# Group_Project_PCB_Updated.net
KiCad netlist of a schematic drawn in EAGLE
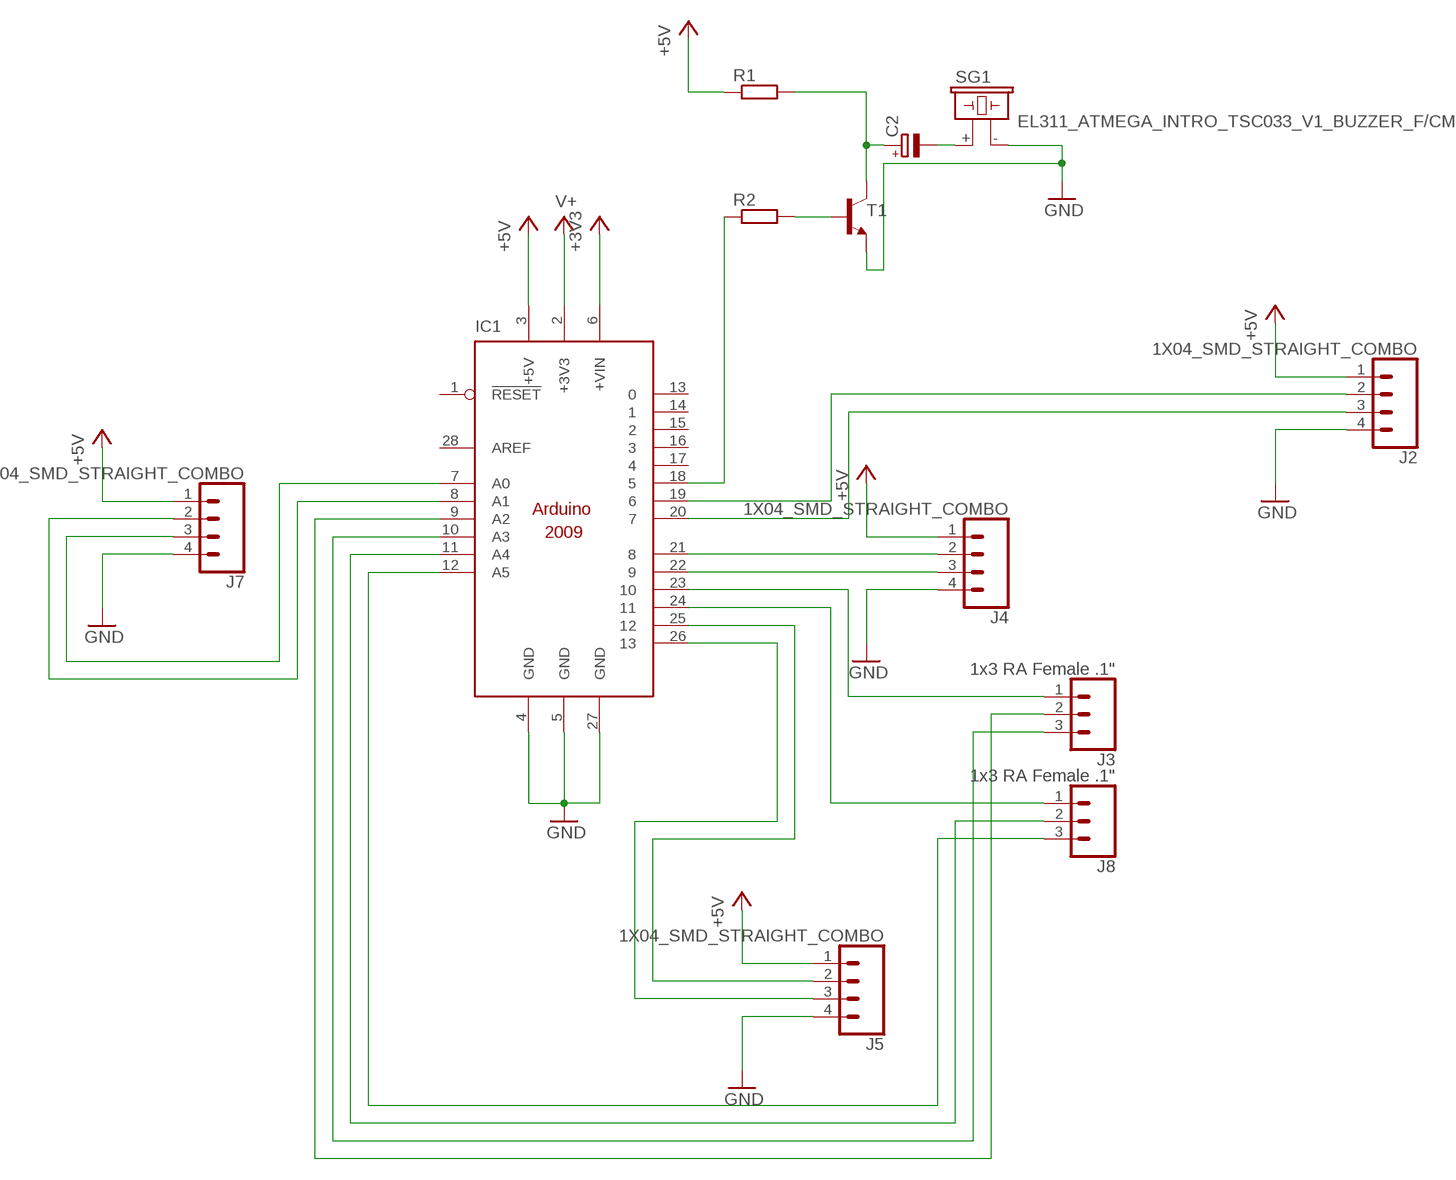
[diagram p0: schematic, sheet 1]

(export (version "E")
  (design (tool "Eeschema 10.0.6"))
  (components
    (comp (ref "C2")
      (value "RCL_CPOL-EUE3.5-8")
      (footprint "eagle-import:ELECTROLYTIC_CAP_RCL_E3,5-8")
      (libsource (lib "eagle-import") (part "RCL_CPOL-EUE3.5-8"))
    )
    (comp (ref "IC1")
      (value "ARDUINO2009_10")
      (footprint "eagle-import:ARDUINO2009")
      (libsource (lib "eagle-import") (part "ARDUINO2009_10"))
    )
    (comp (ref "J2")
      (value "1X04_SMD_STRAIGHT_COMBO")
      (footprint "eagle-import:1X04_LONGPADS")
      (libsource (lib "eagle-import") (part "CONN_04LONGPADS"))
    )
    (comp (ref "J3")
      (value "1x3 RA Female .1\"")
      (footprint "eagle-import:1X03_LONGPADS")
      (libsource (lib "eagle-import") (part "CONN_03LONGPADS"))
    )
    (comp (ref "J4")
      (value "1X04_SMD_STRAIGHT_COMBO")
      (footprint "eagle-import:1X04_LONGPADS")
      (libsource (lib "eagle-import") (part "CONN_04LONGPADS"))
    )
    (comp (ref "J5")
      (value "1X04_SMD_STRAIGHT_COMBO")
      (footprint "eagle-import:1X04_LONGPADS")
      (libsource (lib "eagle-import") (part "CONN_04LONGPADS"))
    )
    (comp (ref "J7")
      (value "1X04_SMD_STRAIGHT_COMBO")
      (footprint "eagle-import:1X04_LONGPADS")
      (libsource (lib "eagle-import") (part "CONN_04LONGPADS"))
    )
    (comp (ref "J8")
      (value "1x3 RA Female .1\"")
      (footprint "eagle-import:1X03_LONGPADS")
      (libsource (lib "eagle-import") (part "CONN_03LONGPADS"))
    )
    (comp (ref "R1")
      (value "R-EU_0207/10")
      (footprint "eagle-import:0207_10")
      (libsource (lib "eagle-import") (part "R-EU_0207/10"))
    )
    (comp (ref "R2")
      (value "R-EU_0207/10")
      (footprint "eagle-import:0207_10")
      (libsource (lib "eagle-import") (part "R-EU_0207/10"))
    )
    (comp (ref "SG1")
      (value "EL311_ATMEGA_INTRO_TSC033_V1_BUZZER_F/CM12P")
      (footprint "eagle-import:EL311_ATMEGA_INTRO_TSC033_V1_BUZZER_F_CM12P")
      (libsource (lib "eagle-import") (part "EL311_ATMEGA_INTRO_TSC033_V1_BUZZER_F/CM12P"))
    )
    (comp (ref "T1")
      (value "2N1613-NPN-TO92-EBC")
      (footprint "eagle-import:TO92-EBC")
      (libsource (lib "eagle-import") (part "-NPN-TO92-EBC2N1613"))
    )
  )
  (nets
    (net (code "1") (name "+3V3") (class "Default")
      (node (ref "IC1") (pin "6") (pinfunction "+VIN_6") (pintype "bidirectional"))
    )
    (net (code "2") (name "+5V") (class "Default")
      (node (ref "IC1") (pin "3") (pinfunction "+5V_3") (pintype "power_in"))
      (node (ref "J2") (pin "1") (pinfunction "1_1") (pintype "passive"))
      (node (ref "J4") (pin "1") (pinfunction "1_1") (pintype "passive"))
      (node (ref "J5") (pin "1") (pinfunction "1_1") (pintype "passive"))
      (node (ref "J7") (pin "1") (pinfunction "1_1") (pintype "passive"))
      (node (ref "R1") (pin "1") (pinfunction "1_1") (pintype "passive"))
    )
    (net (code "3") (name "GND") (class "Default")
      (node (ref "IC1") (pin "27") (pinfunction "GND_27") (pintype "power_in"))
      (node (ref "IC1") (pin "4") (pinfunction "GND_4") (pintype "power_in"))
      (node (ref "IC1") (pin "5") (pinfunction "GND_5") (pintype "power_in"))
      (node (ref "J2") (pin "4") (pinfunction "4_4") (pintype "passive"))
      (node (ref "J4") (pin "4") (pinfunction "4_4") (pintype "passive"))
      (node (ref "J5") (pin "4") (pinfunction "4_4") (pintype "passive"))
      (node (ref "J7") (pin "4") (pinfunction "4_4") (pintype "passive"))
      (node (ref "SG1") (pin "-") (pinfunction "2_-") (pintype "passive"))
      (node (ref "T1") (pin "E") (pinfunction "E_E") (pintype "passive"))
    )
    (net (code "4") (name "Net-(C2-Pad+)") (class "Default")
      (node (ref "C2") (pin "+") (pinfunction "+_+") (pintype "passive"))
      (node (ref "R1") (pin "2") (pinfunction "2_2") (pintype "passive"))
      (node (ref "T1") (pin "C") (pinfunction "C_C") (pintype "passive"))
    )
    (net (code "5") (name "Net-(IC1-5)") (class "Default")
      (node (ref "IC1") (pin "18") (pinfunction "5_18") (pintype "bidirectional"))
      (node (ref "R2") (pin "1") (pinfunction "1_1") (pintype "passive"))
    )
    (net (code "6") (name "Net-(IC1-6)") (class "Default")
      (node (ref "IC1") (pin "19") (pinfunction "6_19") (pintype "bidirectional"))
      (node (ref "J2") (pin "2") (pinfunction "2_2") (pintype "passive"))
    )
    (net (code "7") (name "Net-(IC1-7)") (class "Default")
      (node (ref "IC1") (pin "20") (pinfunction "7_20") (pintype "bidirectional"))
      (node (ref "J2") (pin "3") (pinfunction "3_3") (pintype "passive"))
    )
    (net (code "8") (name "Net-(IC1-8)") (class "Default")
      (node (ref "IC1") (pin "21") (pinfunction "8_21") (pintype "bidirectional"))
      (node (ref "J4") (pin "2") (pinfunction "2_2") (pintype "passive"))
    )
    (net (code "9") (name "Net-(IC1-9)") (class "Default")
      (node (ref "IC1") (pin "22") (pinfunction "9_22") (pintype "bidirectional"))
      (node (ref "J4") (pin "3") (pinfunction "3_3") (pintype "passive"))
    )
    (net (code "10") (name "Net-(IC1-10)") (class "Default")
      (node (ref "IC1") (pin "23") (pinfunction "10_23") (pintype "bidirectional"))
      (node (ref "J3") (pin "1") (pinfunction "1_1") (pintype "passive"))
    )
    (net (code "11") (name "Net-(IC1-11)") (class "Default")
      (node (ref "IC1") (pin "24") (pinfunction "11_24") (pintype "bidirectional"))
      (node (ref "J8") (pin "1") (pinfunction "1_1") (pintype "passive"))
    )
    (net (code "12") (name "Net-(IC1-12)") (class "Default")
      (node (ref "IC1") (pin "25") (pinfunction "12_25") (pintype "bidirectional"))
      (node (ref "J5") (pin "2") (pinfunction "2_2") (pintype "passive"))
    )
    (net (code "13") (name "Net-(IC1-13)") (class "Default")
      (node (ref "IC1") (pin "26") (pinfunction "13_26") (pintype "bidirectional"))
      (node (ref "J5") (pin "3") (pinfunction "3_3") (pintype "passive"))
    )
    (net (code "14") (name "Net-(IC1-A0)") (class "Default")
      (node (ref "IC1") (pin "7") (pinfunction "A0_7") (pintype "bidirectional"))
      (node (ref "J7") (pin "3") (pinfunction "3_3") (pintype "passive"))
    )
    (net (code "15") (name "Net-(IC1-A1)") (class "Default")
      (node (ref "IC1") (pin "8") (pinfunction "A1_8") (pintype "bidirectional"))
      (node (ref "J7") (pin "2") (pinfunction "2_2") (pintype "passive"))
    )
    (net (code "16") (name "Net-(IC1-A2)") (class "Default")
      (node (ref "IC1") (pin "9") (pinfunction "A2_9") (pintype "bidirectional"))
      (node (ref "J3") (pin "2") (pinfunction "2_2") (pintype "passive"))
    )
    (net (code "17") (name "Net-(IC1-A3)") (class "Default")
      (node (ref "IC1") (pin "10") (pinfunction "A3_10") (pintype "bidirectional"))
      (node (ref "J3") (pin "3") (pinfunction "3_3") (pintype "passive"))
    )
    (net (code "18") (name "Net-(IC1-A4)") (class "Default")
      (node (ref "IC1") (pin "11") (pinfunction "A4_11") (pintype "bidirectional"))
      (node (ref "J8") (pin "2") (pinfunction "2_2") (pintype "passive"))
    )
    (net (code "19") (name "Net-(IC1-A5)") (class "Default")
      (node (ref "IC1") (pin "12") (pinfunction "A5_12") (pintype "bidirectional"))
      (node (ref "J8") (pin "3") (pinfunction "3_3") (pintype "passive"))
    )
    (net (code "20") (name "Net-(R2-Pad2)") (class "Default")
      (node (ref "R2") (pin "2") (pinfunction "2_2") (pintype "passive"))
      (node (ref "T1") (pin "B") (pinfunction "B_B") (pintype "passive"))
    )
    (net (code "21") (name "Net-(SG1-1)") (class "Default")
      (node (ref "C2") (pin "-") (pinfunction "-_-") (pintype "passive"))
      (node (ref "SG1") (pin "+") (pinfunction "1_+") (pintype "passive"))
    )
    (net (code "22") (name "V+") (class "Default")
      (node (ref "IC1") (pin "2") (pinfunction "+3V3_2") (pintype "power_in"))
    )
    (net (code "23") (name "unconnected-(IC1-0-Pad13)") (class "Default")
      (node (ref "IC1") (pin "13") (pinfunction "0_13") (pintype "bidirectional"))
    )
    (net (code "24") (name "unconnected-(IC1-1-Pad14)") (class "Default")
      (node (ref "IC1") (pin "14") (pinfunction "1_14") (pintype "bidirectional"))
    )
    (net (code "25") (name "unconnected-(IC1-2-Pad15)") (class "Default")
      (node (ref "IC1") (pin "15") (pinfunction "2_15") (pintype "bidirectional"))
    )
    (net (code "26") (name "unconnected-(IC1-3-Pad16)") (class "Default")
      (node (ref "IC1") (pin "16") (pinfunction "3_16") (pintype "bidirectional"))
    )
    (net (code "27") (name "unconnected-(IC1-4-Pad17)") (class "Default")
      (node (ref "IC1") (pin "17") (pinfunction "4_17") (pintype "bidirectional"))
    )
    (net (code "28") (name "unconnected-(IC1-AREF-Pad28)") (class "Default")
      (node (ref "IC1") (pin "28") (pinfunction "AREF_28") (pintype "bidirectional"))
    )
    (net (code "29") (name "unconnected-(IC1-~{RESET}-Pad1)") (class "Default")
      (node (ref "IC1") (pin "1") (pinfunction "~{RESET}_1") (pintype "bidirectional"))
    )
  )
)
